# Power_Management.net
KiCad netlist of a schematic drawn in Altium Designer
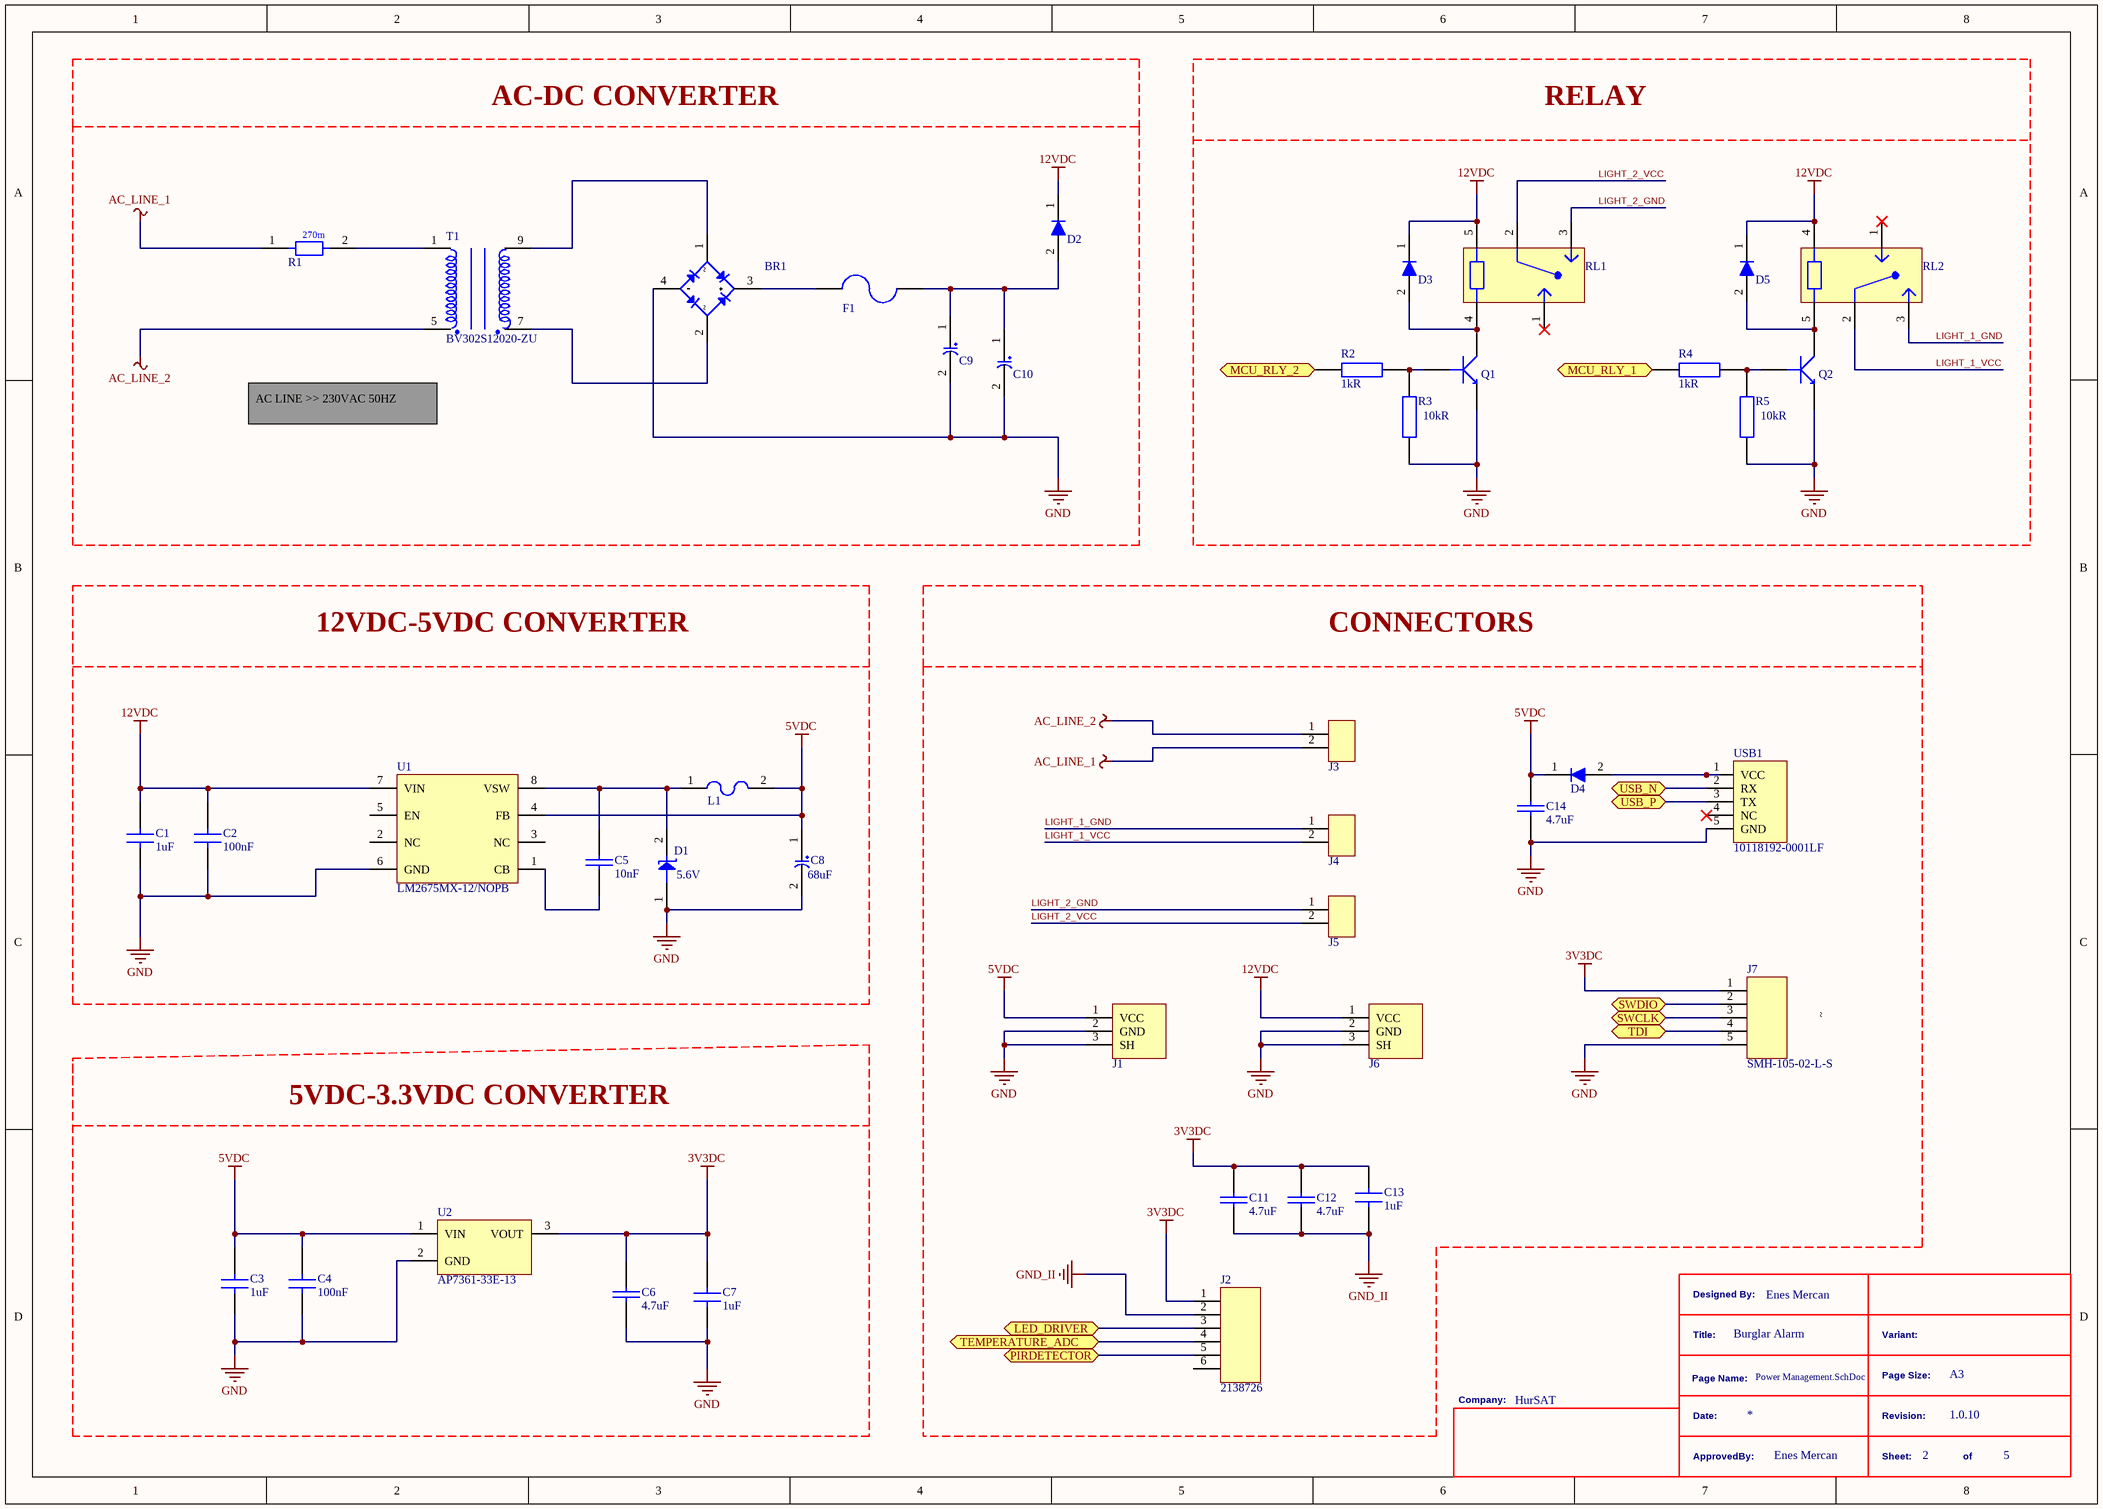
[diagram p0: Power Management.SchDoc]

(export (version "E")
  (design (tool "Eeschema 10.0.6"))
  (components
    (comp (ref "BR1")
      (value "DB105STR")
      (footprint "DB105STR")
      (description "Bridge Rectifier Single Phase Standard 600 V Surface Mount DB-S")
      (fields (field (name "MANUFACTURER") "SMC") (field (name "DESIGNEDBY") "ENES"))
      (libsource (lib "SecurityBoard") (part "DB105STR"))
    )
    (comp (ref "C1")
      (value "CL21B105KBFNNNE")
      (footprint "CAP_0805")
      (fields
        (field (name "MANUFACTURER") "Samsung")
        (field (name "TOLERANCE") "10%")
        (field (name "VOLTAGE") "50V")
        (field (name "CAPACITANCE") "1uF")
      )
      (libsource (lib "SecurityBoard") (part "CAP CER 1uF 0805"))
    )
    (comp (ref "C2")
      (value "C0603X104K4RACTU")
      (footprint "cap_0603")
      (description "CAP CER 0.1UF 16V X7R 0603")
      (fields
        (field (name "MANUFACTURER") "KEMET")
        (field (name "TOLERANCE") "10%")
        (field (name "CAPACITANCE") "100nF")
        (field (name "DESIGNEDBY") "ENES")
      )
      (libsource (lib "SecurityBoard") (part "CAP CER 100nF  0603"))
    )
    (comp (ref "C3")
      (value "CL21B105KBFNNNE")
      (footprint "CAP_0805")
      (fields
        (field (name "MANUFACTURER") "Samsung")
        (field (name "TOLERANCE") "10%")
        (field (name "VOLTAGE") "50V")
        (field (name "CAPACITANCE") "1uF")
      )
      (libsource (lib "SecurityBoard") (part "CAP CER 1uF 0805"))
    )
    (comp (ref "C4")
      (value "C0603X104K4RACTU")
      (footprint "cap_0603")
      (description "CAP CER 0.1UF 16V X7R 0603")
      (fields
        (field (name "MANUFACTURER") "KEMET")
        (field (name "TOLERANCE") "10%")
        (field (name "CAPACITANCE") "100nF")
        (field (name "DESIGNEDBY") "ENES")
      )
      (libsource (lib "SecurityBoard") (part "CAP CER 100nF  0603"))
    )
    (comp (ref "C5")
      (value "0603B103K160CT")
      (footprint "cap_0603")
      (fields
        (field (name "MANUFACTURER") "Walsin Technologies")
        (field (name "TOLERANCE") "10%")
        (field (name "CAPACITANCE") "10nF")
      )
      (libsource (lib "SecurityBoard") (part "CAP CER 10nF 0603"))
    )
    (comp (ref "C6")
      (value "CL21A475KAQNNNE")
      (footprint "CAP_0805")
      (description "CAP CER 4.7uF %10 0805")
      (fields
        (field (name "MANUFACTURER") "Samsung")
        (field (name "TOLERANCE") "10%")
        (field (name "CAPACITANCE") "4.7uF")
      )
      (libsource (lib "SecurityBoard") (part "CAP CER 4.7uF 0805"))
    )
    (comp (ref "C7")
      (value "CL21B105KBFNNNE")
      (footprint "CAP_0805")
      (fields
        (field (name "MANUFACTURER") "Samsung")
        (field (name "TOLERANCE") "10%")
        (field (name "VOLTAGE") "50V")
        (field (name "CAPACITANCE") "1uF")
      )
      (libsource (lib "SecurityBoard") (part "CAP CER 1uF 0805"))
    )
    (comp (ref "C8")
      (value "CAP ALUM 68UF 20% 35V SMD")
      (footprint "CAP_EEVSERIES")
      (description "Cap Aluminum Lytic 68uF 35V 20% (6.3 X 7.7mm) SMD 280mA 2000h 105C T/R")
      (fields
        (field (name "MANUFACTURER") "KEMET")
        (field (name "MANUFACTURER PART NUMBER") "EEV686M035A9HAA")
        (field (name "CAPACITANCE") "68uF")
      )
      (libsource (lib "SecurityBoard") (part "CAP ALUM 68UF"))
    )
    (comp (ref "C9")
      (value "ESY277M050AH4AA")
      (footprint "CAP_RADIAL_D10P5")
      (description "Cap, 470UF, 50V, Alu Elec, Radial")
      (fields
        (field (name "MANUFACTURER") "KEMET")
        (field (name "MANUFACTURER PART NUMBER") "ESH477M050AH4AA")
      )
      (libsource (lib "SecurityBoard") (part "ESY277M050AH4AA"))
    )
    (comp (ref "C10")
      (value "ESY277M050AH4AA")
      (footprint "CAP_RADIAL_D10P5")
      (description "Cap, 470UF, 50V, Alu Elec, Radial")
      (fields
        (field (name "MANUFACTURER") "KEMET")
        (field (name "MANUFACTURER PART NUMBER") "ESH477M050AH4AA")
      )
      (libsource (lib "SecurityBoard") (part "ESY277M050AH4AA"))
    )
    (comp (ref "C11")
      (value "CL21A475KAQNNNE")
      (footprint "CAP_0805")
      (description "CAP CER 4.7uF %10 0805")
      (fields
        (field (name "MANUFACTURER") "Samsung")
        (field (name "TOLERANCE") "10%")
        (field (name "CAPACITANCE") "4.7uF")
      )
      (libsource (lib "SecurityBoard") (part "CAP CER 4.7uF 0805"))
    )
    (comp (ref "C12")
      (value "CL21A475KAQNNNE")
      (footprint "CAP_0805")
      (description "CAP CER 4.7uF %10 0805")
      (fields
        (field (name "MANUFACTURER") "Samsung")
        (field (name "TOLERANCE") "10%")
        (field (name "CAPACITANCE") "4.7uF")
      )
      (libsource (lib "SecurityBoard") (part "CAP CER 4.7uF 0805"))
    )
    (comp (ref "C13")
      (value "CL21B105KBFNNNE")
      (footprint "CAP_0805")
      (fields
        (field (name "MANUFACTURER") "Samsung")
        (field (name "TOLERANCE") "10%")
        (field (name "VOLTAGE") "50V")
        (field (name "CAPACITANCE") "1uF")
      )
      (libsource (lib "SecurityBoard") (part "CAP CER 1uF 0805"))
    )
    (comp (ref "C14")
      (value "CL21A475KAQNNNE")
      (footprint "CAP_0805")
      (description "CAP CER 4.7uF %10 0805")
      (fields
        (field (name "MANUFACTURER") "Samsung")
        (field (name "TOLERANCE") "10%")
        (field (name "CAPACITANCE") "4.7uF")
      )
      (libsource (lib "SecurityBoard") (part "CAP CER 4.7uF 0805"))
    )
    (comp (ref "D1")
      (value "1SMB5919BT3G")
      (footprint "1SMB5919BT3G")
      (description "Diode Zener Single 5.6V 5% 3W 2-Pin SMB T/R")
      (fields
        (field (name "MANUFACTURER") "ON Semiconductor")
        (field (name "TOLERANCE") "5%")
        (field (name "ZENER VOLTAGE") "5.6V")
      )
      (libsource (lib "SecurityBoard") (part "1SMB5919BT3G"))
    )
    (comp (ref "D2")
      (value "1N4148WS")
      (footprint "1N4148WS")
      (description "ON SEMICONDUCTOR - 1N4148WS - Small Signal Diode, Single, 75 V, 150 mA, 1 V, 4 ns")
      (fields (field (name "MANUFACTURER") "ON Semiconductor / Fairchild"))
      (libsource (lib "SecurityBoard") (part "1N4148WS"))
    )
    (comp (ref "D3")
      (value "1N4148WS")
      (footprint "1N4148WS")
      (description "ON SEMICONDUCTOR - 1N4148WS - Small Signal Diode, Single, 75 V, 150 mA, 1 V, 4 ns")
      (fields (field (name "MANUFACTURER") "ON Semiconductor / Fairchild"))
      (libsource (lib "SecurityBoard") (part "1N4148WS"))
    )
    (comp (ref "D4")
      (value "1N4148WS")
      (footprint "1N4148WS")
      (description "ON SEMICONDUCTOR - 1N4148WS - Small Signal Diode, Single, 75 V, 150 mA, 1 V, 4 ns")
      (fields (field (name "MANUFACTURER") "ON Semiconductor / Fairchild"))
      (libsource (lib "SecurityBoard") (part "1N4148WS"))
    )
    (comp (ref "D5")
      (value "1N4148WS")
      (footprint "1N4148WS")
      (description "ON SEMICONDUCTOR - 1N4148WS - Small Signal Diode, Single, 75 V, 150 mA, 1 V, 4 ns")
      (fields (field (name "MANUFACTURER") "ON Semiconductor / Fairchild"))
      (libsource (lib "SecurityBoard") (part "1N4148WS"))
    )
    (comp (ref "F1")
      (value "3413.0216.22")
      (footprint "3413.0216.22")
      (description "FUSE BRD MNT 1A 32VAC 63VDC 1206")
      (fields (field (name "MANUFACTURER") "Schurter"))
      (libsource (lib "SecurityBoard") (part "Fuse 3413.0216.22"))
    )
    (comp (ref "J1")
      (value "PJ-037AH-SMT-TR")
      (footprint "JACK")
      (description "DC Power Connectors Power Jacks")
      (fields (field (name "MANUFACTURER") "CUI"))
      (libsource (lib "SecurityBoard") (part "PJ-037AH-SMT-TR"))
    )
    (comp (ref "J2")
      (value "64800611622")
      (footprint "64800611622")
      (fields
        (field (name "MANUFACTURER") "Wurth Electronics")
        (field (name "SUPPLIER PART NUMBER 1") "2138726")
      )
      (libsource (lib "SecurityBoard") (part "64800611622_conn_6pin"))
    )
    (comp (ref "J3")
      (value "TBP01R1-508-02BE")
      (footprint "TBP01R1-508")
      (description "Conn Shrouded Header HDR 2 POS 5.08mm Solder RA Side Entry Thru-Hole Bag")
      (fields (field (name "MANUFACTURER") "CUI"))
      (libsource (lib "SecurityBoard") (part "TBP01R1-508-02BE"))
    )
    (comp (ref "J4")
      (value "TBP01R1-508-02BE")
      (footprint "TBP01R1-508")
      (description "Conn Shrouded Header HDR 2 POS 5.08mm Solder RA Side Entry Thru-Hole Bag")
      (fields (field (name "MANUFACTURER") "CUI"))
      (libsource (lib "SecurityBoard") (part "TBP01R1-508-02BE"))
    )
    (comp (ref "J5")
      (value "TBP01R1-508-02BE")
      (footprint "TBP01R1-508")
      (description "Conn Shrouded Header HDR 2 POS 5.08mm Solder RA Side Entry Thru-Hole Bag")
      (fields (field (name "MANUFACTURER") "CUI"))
      (libsource (lib "SecurityBoard") (part "TBP01R1-508-02BE"))
    )
    (comp (ref "J6")
      (value "PJ-037AH-SMT-TR")
      (footprint "JACK")
      (description "DC Power Connectors Power Jacks")
      (fields (field (name "MANUFACTURER") "CUI"))
      (libsource (lib "SecurityBoard") (part "PJ-037AH-SMT-TR"))
    )
    (comp (ref "J7")
      (value "SMH-105-02-L-S")
      (footprint "PINHEADER1X5_RA")
      (description ".100 C.L. HORIZONTAL SMT SOCKET")
      (fields (field (name "MANUFACTURER") "Samtec"))
      (libsource (lib "SecurityBoard") (part "SMH-105-02-L-S"))
    )
    (comp (ref "L1")
      (value "78438335470")
      (footprint "IND_1212")
      (description "FIXED IND 47UH 390MA 2.3 OHM SMD")
      (fields (field (name "MANUFACTURER") "Wurth Electronics") (field (name "TOLERANCE") "30%"))
      (libsource (lib "SecurityBoard") (part "IND 47uH"))
    )
    (comp (ref "Q1")
      (value "MMBT3904-7-F")
      (footprint "MMBT3904-7-F")
      (description "Transistor General Purpose BJT NPN 40 Volt 0.2A Automotive 3-Pin SOT-23")
      (fields (field (name "MANUFACTURER") "Diodes Zetex"))
      (libsource (lib "SecurityBoard") (part "MMBT3904-7-F"))
    )
    (comp (ref "Q2")
      (value "MMBT3904-7-F")
      (footprint "MMBT3904-7-F")
      (description "Transistor General Purpose BJT NPN 40 Volt 0.2A Automotive 3-Pin SOT-23")
      (fields (field (name "MANUFACTURER") "Diodes Zetex"))
      (libsource (lib "SecurityBoard") (part "MMBT3904-7-F"))
    )
    (comp (ref "R1")
      (value "5WD27")
      (footprint "RES_AXIAL_W")
      (description "RESISTOR 5 WATT CERMET WIREWOUND FLAMEPROOF .27 OHM 5% AXIAL LEAD")
      (fields (field (name "MANUFACTURER") "NTE Electronics") (field (name "TOLERANCE") "5%"))
      (libsource (lib "SecurityBoard") (part "5WD27"))
    )
    (comp (ref "R2")
      (value "AC0603FR-071KL")
      (footprint "res_0603")
      (description "Res Thick Film 0603 1K Ohm 1% 0.1W(1/10W) ±100ppm/C Epoxy Pad SMD Automotive T/R")
      (fields
        (field (name "MANUFACTURER") "Yageo")
        (field (name "TOLERANCE") "1%")
        (field (name "RESISTANCE") "1kR")
      )
      (libsource (lib "SecurityBoard") (part "RES 1K OHM 0603"))
    )
    (comp (ref "R3")
      (value "RC0603FR-0710KL")
      (footprint "res_0603")
      (description "Res General Purpose Thick Film 0603 10K Ohm 1% 1/10W ±100ppm/°C Molded SMD Paper T/R")
      (fields
        (field (name "MANUFACTURER") "Yageo")
        (field (name "TOLERANCE") "1%")
        (field (name "RESISTANCE") "10kR")
      )
      (libsource (lib "SecurityBoard") (part "RES 10K OHM 0603"))
    )
    (comp (ref "R4")
      (value "AC0603FR-071KL")
      (footprint "res_0603")
      (description "Res Thick Film 0603 1K Ohm 1% 0.1W(1/10W) ±100ppm/C Epoxy Pad SMD Automotive T/R")
      (fields
        (field (name "MANUFACTURER") "Yageo")
        (field (name "TOLERANCE") "1%")
        (field (name "RESISTANCE") "1kR")
      )
      (libsource (lib "SecurityBoard") (part "RES 1K OHM 0603"))
    )
    (comp (ref "R5")
      (value "RC0603FR-0710KL")
      (footprint "res_0603")
      (description "Res General Purpose Thick Film 0603 10K Ohm 1% 1/10W ±100ppm/°C Molded SMD Paper T/R")
      (fields
        (field (name "MANUFACTURER") "Yageo")
        (field (name "TOLERANCE") "1%")
        (field (name "RESISTANCE") "10kR")
      )
      (libsource (lib "SecurityBoard") (part "RES 10K OHM 0603"))
    )
    (comp (ref "RL1")
      (value "ALQ112")
      (footprint "ALQ112")
      (description "PANASONIC - ALQ112 - POWER RELAY, SPDT, 12VDC, 10A, THD")
      (fields (field (name "MANUFACTURER") "Panasonic") (field (name "DESIGNEDBY") "ENES"))
      (libsource (lib "") (part "ALQ112_1"))
    )
    (comp (ref "RL2")
      (value "ALQ112")
      (footprint "ALQ112")
      (description "PANASONIC - ALQ112 - POWER RELAY, SPDT, 12VDC, 10A, THD")
      (fields (field (name "MANUFACTURER") "Panasonic") (field (name "DESIGNEDBY") "ENES"))
      (libsource (lib "SecurityBoard") (part "ALQ112"))
    )
    (comp (ref "T1")
      (value "BV302S12020-ZU")
      (footprint "BV302S12020-ZU")
      (description "PWR XFMR LAMINATED 2VA TH")
      (fields (field (name "MANUFACTURER") "Zettler Magnetics") (field (name "DESIGNEDBY") "ENES"))
      (libsource (lib "SecurityBoard") (part "BV302S12020-ZU"))
    )
    (comp (ref "U1")
      (value "LM2675MX-12/NOPB")
      (footprint "SOIC8")
      (description "Switching Voltage Regulators Pwr Cnvtr Hi Eff 1A SD Vtg Reg")
      (fields (field (name "MANUFACTURER") "TI National Semiconductor"))
      (libsource (lib "SecurityBoard") (part "LM2675MX-12/NOPB"))
    )
    (comp (ref "U2")
      (value "AP7361-33E-13")
      (footprint "SOT223")
      (description "LDO Regulator Pos 3.3V 1A 4-Pin(3+Tab) SOT-223 T/R")
      (fields (field (name "MANUFACTURER") "Diodes") (field (name "DESIGNEDBY") "ENES"))
      (libsource (lib "SecurityBoard") (part "AP7361-33E-13"))
    )
    (comp (ref "USB1")
      (value "10118192-0001LF")
      (footprint "MICRO_B_USB")
      (description "CONN USB MICRO B RECPT SMT R/A")
      (fields (field (name "MANUFACTURER") "Amphenol ICC / FCI"))
      (libsource (lib "SecurityBoard") (part "Micro B USB Connector"))
    )
  )
  (nets
    (net (code "1") (name "/LED_DRIVER") (class "Default")
      (node (ref "J2") (pin "3") (pinfunction "3_3") (pintype "passive"))
    )
    (net (code "2") (name "/LIGHT_1_GND") (class "Default")
      (node (ref "J4") (pin "1") (pinfunction "1_1") (pintype "power_in"))
      (node (ref "RL2") (pin "3") (pinfunction "3_3") (pintype "passive"))
    )
    (net (code "3") (name "/LIGHT_1_VCC") (class "Default")
      (node (ref "J4") (pin "2") (pinfunction "2_2") (pintype "power_in"))
      (node (ref "RL2") (pin "2") (pinfunction "2_2") (pintype "passive"))
    )
    (net (code "4") (name "/LIGHT_2_GND") (class "Default")
      (node (ref "J5") (pin "1") (pinfunction "1_1") (pintype "power_in"))
      (node (ref "RL1") (pin "3") (pinfunction "3_3") (pintype "passive"))
    )
    (net (code "5") (name "/LIGHT_2_VCC") (class "Default")
      (node (ref "J5") (pin "2") (pinfunction "2_2") (pintype "power_in"))
      (node (ref "RL1") (pin "2") (pinfunction "2_2") (pintype "passive"))
    )
    (net (code "6") (name "/MCU_RLY_1") (class "Default")
      (node (ref "R4") (pin "1") (pinfunction "1_1") (pintype "passive"))
    )
    (net (code "7") (name "/MCU_RLY_2") (class "Default")
      (node (ref "R2") (pin "1") (pinfunction "1_1") (pintype "passive"))
    )
    (net (code "8") (name "/PIRDETECTOR") (class "Default")
      (node (ref "J2") (pin "5") (pinfunction "5_5") (pintype "passive"))
    )
    (net (code "9") (name "/SWCLK") (class "Default")
      (node (ref "J7") (pin "3") (pinfunction "3_3") (pintype "passive"))
    )
    (net (code "10") (name "/SWDIO") (class "Default")
      (node (ref "J7") (pin "2") (pinfunction "2_2") (pintype "passive"))
    )
    (net (code "11") (name "/TDI") (class "Default")
      (node (ref "J7") (pin "4") (pinfunction "4_4") (pintype "passive"))
    )
    (net (code "12") (name "/TEMPERATURE_ADC") (class "Default")
      (node (ref "J2") (pin "4") (pinfunction "4_4") (pintype "passive"))
    )
    (net (code "13") (name "/USB_N") (class "Default")
      (node (ref "USB1") (pin "2") (pinfunction "RX_2") (pintype "passive"))
    )
    (net (code "14") (name "/USB_P") (class "Default")
      (node (ref "USB1") (pin "3") (pinfunction "TX_3") (pintype "passive"))
    )
    (net (code "15") (name "3V3DC") (class "Default")
      (node (ref "C11") (pin "2") (pinfunction "2_2") (pintype "passive"))
      (node (ref "C12") (pin "2") (pinfunction "2_2") (pintype "passive"))
      (node (ref "C13") (pin "2") (pinfunction "2_2") (pintype "passive"))
      (node (ref "C6") (pin "1") (pinfunction "1_1") (pintype "passive"))
      (node (ref "C7") (pin "1") (pinfunction "1_1") (pintype "passive"))
      (node (ref "J2") (pin "1") (pinfunction "1_1") (pintype "passive"))
      (node (ref "J7") (pin "1") (pinfunction "1_1") (pintype "passive"))
      (node (ref "U2") (pin "3") (pinfunction "VOUT_3") (pintype "passive"))
    )
    (net (code "16") (name "5VDC") (class "Default")
      (node (ref "C14") (pin "1") (pinfunction "1_1") (pintype "passive"))
      (node (ref "C3") (pin "1") (pinfunction "1_1") (pintype "passive"))
      (node (ref "C4") (pin "1") (pinfunction "1_1") (pintype "passive"))
      (node (ref "C8") (pin "1") (pinfunction "1_1") (pintype "passive"))
      (node (ref "D4") (pin "1") (pinfunction "1_1") (pintype "passive"))
      (node (ref "J1") (pin "1") (pinfunction "VCC_1") (pintype "passive"))
      (node (ref "L1") (pin "2") (pinfunction "2_2") (pintype "passive"))
      (node (ref "U1") (pin "4") (pinfunction "FB_4") (pintype "passive"))
      (node (ref "U2") (pin "1") (pinfunction "VIN_1") (pintype "passive"))
    )
    (net (code "17") (name "12VDC") (class "Default")
      (node (ref "C1") (pin "1") (pinfunction "1_1") (pintype "passive"))
      (node (ref "C2") (pin "1") (pinfunction "1_1") (pintype "passive"))
      (node (ref "D2") (pin "1") (pinfunction "1_1") (pintype "passive"))
      (node (ref "D3") (pin "1") (pinfunction "1_1") (pintype "passive"))
      (node (ref "D5") (pin "1") (pinfunction "1_1") (pintype "passive"))
      (node (ref "J6") (pin "1") (pinfunction "VCC_1") (pintype "passive"))
      (node (ref "RL1") (pin "5") (pinfunction "5_5") (pintype "passive"))
      (node (ref "RL2") (pin "4") (pinfunction "4_4") (pintype "passive"))
      (node (ref "U1") (pin "7") (pinfunction "VIN_7") (pintype "passive"))
    )
    (net (code "18") (name "AC_LINE_1") (class "Default")
      (node (ref "J3") (pin "2") (pinfunction "2_2") (pintype "power_in"))
      (node (ref "R1") (pin "1") (pinfunction "1_1") (pintype "passive"))
    )
    (net (code "19") (name "AC_LINE_2") (class "Default")
      (node (ref "J3") (pin "1") (pinfunction "1_1") (pintype "power_in"))
      (node (ref "T1") (pin "5") (pinfunction "5_5") (pintype "passive"))
    )
    (net (code "20") (name "GND") (class "Default")
      (node (ref "BR1") (pin "4") (pinfunction "4_4") (pintype "passive"))
      (node (ref "C1") (pin "2") (pinfunction "2_2") (pintype "passive"))
      (node (ref "C10") (pin "2") (pinfunction "2_2") (pintype "passive"))
      (node (ref "C14") (pin "2") (pinfunction "2_2") (pintype "passive"))
      (node (ref "C2") (pin "2") (pinfunction "2_2") (pintype "passive"))
      (node (ref "C3") (pin "2") (pinfunction "2_2") (pintype "passive"))
      (node (ref "C4") (pin "2") (pinfunction "2_2") (pintype "passive"))
      (node (ref "C6") (pin "2") (pinfunction "2_2") (pintype "passive"))
      (node (ref "C7") (pin "2") (pinfunction "2_2") (pintype "passive"))
      (node (ref "C8") (pin "2") (pinfunction "2_2") (pintype "passive"))
      (node (ref "C9") (pin "2") (pinfunction "2_2") (pintype "passive"))
      (node (ref "D1") (pin "1") (pinfunction "1_1") (pintype "passive"))
      (node (ref "J1") (pin "2") (pinfunction "GND_2") (pintype "passive"))
      (node (ref "J1") (pin "3") (pinfunction "SH_3") (pintype "passive"))
      (node (ref "J6") (pin "2") (pinfunction "GND_2") (pintype "passive"))
      (node (ref "J6") (pin "3") (pinfunction "SH_3") (pintype "passive"))
      (node (ref "J7") (pin "5") (pinfunction "5_5") (pintype "passive"))
      (node (ref "Q1") (pin "E") (pinfunction "E_E") (pintype "passive"))
      (node (ref "Q2") (pin "E") (pinfunction "E_E") (pintype "passive"))
      (node (ref "R3") (pin "1") (pinfunction "1_1") (pintype "passive"))
      (node (ref "R5") (pin "1") (pinfunction "1_1") (pintype "passive"))
      (node (ref "U1") (pin "6") (pinfunction "GND_6") (pintype "passive"))
      (node (ref "U2") (pin "2") (pinfunction "GND_2") (pintype "passive"))
      (node (ref "USB1") (pin "5") (pinfunction "GND_5") (pintype "passive"))
    )
    (net (code "21") (name "GND_II") (class "Default")
      (node (ref "C11") (pin "1") (pinfunction "1_1") (pintype "passive"))
      (node (ref "C12") (pin "1") (pinfunction "1_1") (pintype "passive"))
      (node (ref "C13") (pin "1") (pinfunction "1_1") (pintype "passive"))
      (node (ref "J2") (pin "2") (pinfunction "2_2") (pintype "passive"))
    )
    (net (code "22") (name "Net-(BR1-Pad1)") (class "Default")
      (node (ref "BR1") (pin "1") (pinfunction "1_1") (pintype "passive"))
      (node (ref "T1") (pin "9") (pinfunction "9_9") (pintype "passive"))
    )
    (net (code "23") (name "Net-(BR1-Pad2)") (class "Default")
      (node (ref "BR1") (pin "2") (pinfunction "2_2") (pintype "passive"))
      (node (ref "T1") (pin "7") (pinfunction "7_7") (pintype "passive"))
    )
    (net (code "24") (name "Net-(BR1-Pad3)") (class "Default")
      (node (ref "BR1") (pin "3") (pinfunction "3_3") (pintype "passive"))
      (node (ref "F1") (pin "1") (pinfunction "1_1") (pintype "passive"))
    )
    (net (code "25") (name "Net-(C10-Pad1)") (class "Default")
      (node (ref "C10") (pin "1") (pinfunction "1_1") (pintype "passive"))
      (node (ref "C9") (pin "1") (pinfunction "1_1") (pintype "passive"))
      (node (ref "D2") (pin "2") (pinfunction "2_2") (pintype "passive"))
      (node (ref "F1") (pin "2") (pinfunction "2_2") (pintype "passive"))
    )
    (net (code "26") (name "Net-(D3-Pad2)") (class "Default")
      (node (ref "D3") (pin "2") (pinfunction "2_2") (pintype "passive"))
      (node (ref "Q1") (pin "C") (pinfunction "C_C") (pintype "passive"))
      (node (ref "RL1") (pin "4") (pinfunction "4_4") (pintype "passive"))
    )
    (net (code "27") (name "Net-(D5-Pad2)") (class "Default")
      (node (ref "D5") (pin "2") (pinfunction "2_2") (pintype "passive"))
      (node (ref "Q2") (pin "C") (pinfunction "C_C") (pintype "passive"))
      (node (ref "RL2") (pin "5") (pinfunction "5_5") (pintype "passive"))
    )
    (net (code "28") (name "Net-(Q1-PadB)") (class "Default")
      (node (ref "Q1") (pin "B") (pinfunction "B_B") (pintype "passive"))
      (node (ref "R2") (pin "2") (pinfunction "2_2") (pintype "passive"))
      (node (ref "R3") (pin "2") (pinfunction "2_2") (pintype "passive"))
    )
    (net (code "29") (name "Net-(Q2-PadB)") (class "Default")
      (node (ref "Q2") (pin "B") (pinfunction "B_B") (pintype "passive"))
      (node (ref "R4") (pin "2") (pinfunction "2_2") (pintype "passive"))
      (node (ref "R5") (pin "2") (pinfunction "2_2") (pintype "passive"))
    )
    (net (code "30") (name "Net-(R1-Pad2)") (class "Default")
      (node (ref "R1") (pin "2") (pinfunction "2_2") (pintype "passive"))
      (node (ref "T1") (pin "1") (pinfunction "1_1") (pintype "passive"))
    )
    (net (code "31") (name "Net-(U1-CB)") (class "Default")
      (node (ref "C5") (pin "1") (pinfunction "1_1") (pintype "passive"))
      (node (ref "U1") (pin "1") (pinfunction "CB_1") (pintype "passive"))
    )
    (net (code "32") (name "Net-(U1-VSW)") (class "Default")
      (node (ref "C5") (pin "2") (pinfunction "2_2") (pintype "passive"))
      (node (ref "D1") (pin "2") (pinfunction "2_2") (pintype "passive"))
      (node (ref "L1") (pin "1") (pinfunction "1_1") (pintype "passive"))
      (node (ref "U1") (pin "8") (pinfunction "VSW_8") (pintype "passive"))
    )
    (net (code "33") (name "Net-(USB1-VCC)") (class "Default")
      (node (ref "D4") (pin "2") (pinfunction "2_2") (pintype "passive"))
      (node (ref "USB1") (pin "1") (pinfunction "VCC_1") (pintype "passive"))
    )
    (net (code "34") (name "unconnected-(J2-Pad6)") (class "Default")
      (node (ref "J2") (pin "6") (pinfunction "6_6") (pintype "passive"))
    )
    (net (code "35") (name "unconnected-(RL1-Pad1)") (class "Default")
      (node (ref "RL1") (pin "1") (pinfunction "1_1") (pintype "passive+no_connect"))
    )
    (net (code "36") (name "unconnected-(RL2-Pad1)") (class "Default")
      (node (ref "RL2") (pin "1") (pinfunction "1_1") (pintype "passive+no_connect"))
    )
    (net (code "37") (name "unconnected-(U1-EN-Pad5)") (class "Default")
      (node (ref "U1") (pin "5") (pinfunction "EN_5") (pintype "passive"))
    )
    (net (code "38") (name "unconnected-(U1-NC-Pad2)") (class "Default")
      (node (ref "U1") (pin "2") (pinfunction "NC_2") (pintype "passive"))
    )
    (net (code "39") (name "unconnected-(U1-NC-Pad3)") (class "Default")
      (node (ref "U1") (pin "3") (pinfunction "NC_3") (pintype "passive"))
    )
    (net (code "40") (name "unconnected-(USB1-NC-Pad4)") (class "Default")
      (node (ref "USB1") (pin "4") (pinfunction "NC_4") (pintype "passive+no_connect"))
    )
  )
)
